# THS7002CPWP_Schematic_2.net
KiCad netlist of a schematic drawn in Altium Designer
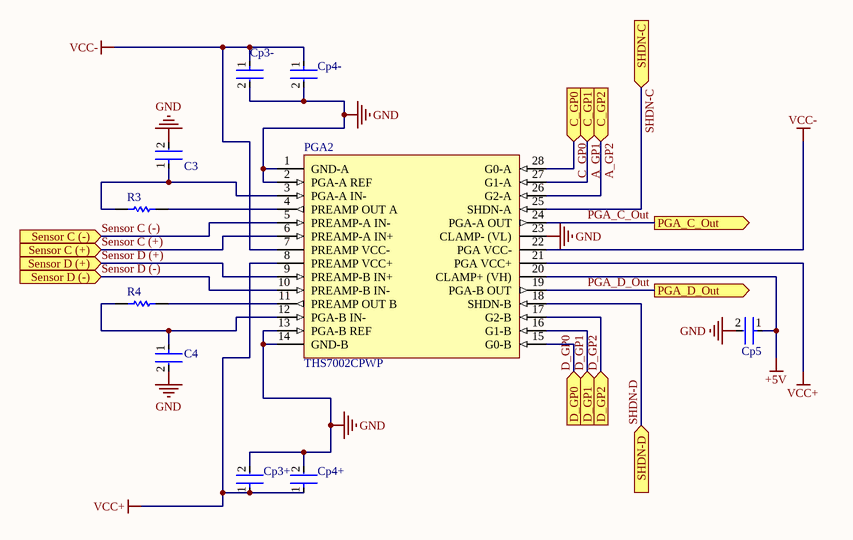
[diagram p0: THS7002CPWP_Schematic_2.SchDoc]

(export (version "E")
  (design (tool "Eeschema 10.0.6"))
  (components
    (comp (ref "C3")
      (value "GRM3195C1H163JA01D")
      (footprint "FP-GRM319-0_15-IPC_A")
      (description "Chip Multilayer Ceramic Capacitors for General Purpose, 1206, 16000pF, C0G, 30ppm/°C, 5%, 50V")
      (fields (field (name "TOLERANCE") "5%"))
      (libsource (lib "Altium Content Vault") (part "b4654b650e69147ec39a6b967a45e02"))
    )
    (comp (ref "C4")
      (value "GRM3195C1H163JA01D")
      (footprint "FP-GRM319-0_15-IPC_A")
      (description "Chip Multilayer Ceramic Capacitors for General Purpose, 1206, 16000pF, C0G, 30ppm/°C, 5%, 50V")
      (fields (field (name "TOLERANCE") "5%"))
      (libsource (lib "Altium Content Vault") (part "b4654b650e69147ec39a6b967a45e02"))
    )
    (comp (ref "Cp3+")
      (value "CC0603KRX7R7BB104")
      (footprint "FP-CC0603-DA-MFG")
      (description "CAP CER 0.1UF 16V X7R 0603")
      (fields
        (field (name "OCTOPART") "https://octopart.com/cc0603krx7r7bb104-yageo-192941")
        (field (name "TOLERANCE") "0.1")
      )
      (libsource (lib "Altium Content Vault") (part "11868f565c42a9108669ba33697ecf6"))
    )
    (comp (ref "Cp3-")
      (value "CC0603KRX7R7BB104")
      (footprint "FP-CC0603-DA-MFG")
      (description "CAP CER 0.1UF 16V X7R 0603")
      (fields
        (field (name "OCTOPART") "https://octopart.com/cc0603krx7r7bb104-yageo-192941")
        (field (name "TOLERANCE") "0.1")
      )
      (libsource (lib "Altium Content Vault") (part "11868f565c42a9108669ba33697ecf6"))
    )
    (comp (ref "Cp4+")
      (value "C2012JB1A685K060AC")
      (footprint "FP-C2012-060-0_2-IPC_A")
      (description "Multilayer Ceramic Capacitors 6.8μF ±10% 10V JB SMD 0805")
      (fields (field (name "TOLERANCE") "10%"))
      (libsource (lib "Altium Content Vault") (part "b4654b650e69147ec39a6b967a45e02"))
    )
    (comp (ref "Cp4-")
      (value "C2012JB1A685K060AC")
      (footprint "FP-C2012-060-0_2-IPC_A")
      (description "Multilayer Ceramic Capacitors 6.8μF ±10% 10V JB SMD 0805")
      (fields (field (name "TOLERANCE") "10%"))
      (libsource (lib "Altium Content Vault") (part "b4654b650e69147ec39a6b967a45e02"))
    )
    (comp (ref "Cp5")
      (value "C2012JB1A685K060AC")
      (footprint "FP-C2012-060-0_2-IPC_A")
      (description "Multilayer Ceramic Capacitors 6.8μF ±10% 10V JB SMD 0805")
      (fields (field (name "TOLERANCE") "10%"))
      (libsource (lib "Altium Content Vault") (part "b4654b650e69147ec39a6b967a45e02"))
    )
    (comp (ref "PGA2")
      (value "THS7002CPWP")
      (footprint "PWP0028E_M")
      (fields (field (name "MANUFACTURER") "Texas Instruments"))
      (libsource (lib "THS7002CPWP_Symbol") (part "CMP-0988-00132-2"))
    )
    (comp (ref "R3")
      (value "CRCW08050000Z0EA")
      (footprint "RESC2013X50X30LL20T20")
      (fields (field (name "MANUFACTURER") "Vishay Dale"))
      (libsource (lib "Altium Content Vault") (part "RES"))
    )
    (comp (ref "R4")
      (value "CRCW08050000Z0EA")
      (footprint "RESC2013X50X30LL20T20")
      (fields (field (name "MANUFACTURER") "Vishay Dale"))
      (libsource (lib "Altium Content Vault") (part "RES"))
    )
  )
  (nets
    (net (code "1") (name "+5V") (class "Default")
      (node (ref "Cp5") (pin "1") (pinfunction "1_1") (pintype "passive"))
      (node (ref "PGA2") (pin "20") (pinfunction "CLAMP+_(VH)_20") (pintype "power_in"))
    )
    (net (code "2") (name "/A_GP1") (class "Default")
      (node (ref "PGA2") (pin "27") (pinfunction "G1-A_27") (pintype "input"))
    )
    (net (code "3") (name "/A_GP2") (class "Default")
      (node (ref "PGA2") (pin "26") (pinfunction "G2-A_26") (pintype "input"))
    )
    (net (code "4") (name "/C_GP0") (class "Default")
      (node (ref "PGA2") (pin "28") (pinfunction "G0-A_28") (pintype "input"))
    )
    (net (code "5") (name "/D_GP0") (class "Default")
      (node (ref "PGA2") (pin "15") (pinfunction "G0-B_15") (pintype "input"))
    )
    (net (code "6") (name "/D_GP1") (class "Default")
      (node (ref "PGA2") (pin "16") (pinfunction "G1-B_16") (pintype "input"))
    )
    (net (code "7") (name "/D_GP2") (class "Default")
      (node (ref "PGA2") (pin "17") (pinfunction "G2-B_17") (pintype "input"))
    )
    (net (code "8") (name "/PGA_C_Out") (class "Default")
      (node (ref "PGA2") (pin "24") (pinfunction "PGA-A_OUT_24") (pintype "output"))
    )
    (net (code "9") (name "/PGA_D_Out") (class "Default")
      (node (ref "PGA2") (pin "19") (pinfunction "PGA-B_OUT_19") (pintype "output"))
    )
    (net (code "10") (name "/SHDN-C") (class "Default")
      (node (ref "PGA2") (pin "25") (pinfunction "SHDN-A_25") (pintype "input"))
    )
    (net (code "11") (name "/SHDN-D") (class "Default")
      (node (ref "PGA2") (pin "18") (pinfunction "SHDN-B_18") (pintype "input"))
    )
    (net (code "12") (name "/Sensor C (+)") (class "Default")
      (node (ref "PGA2") (pin "6") (pinfunction "PREAMP-A_IN+_6") (pintype "input"))
    )
    (net (code "13") (name "/Sensor C (-)") (class "Default")
      (node (ref "PGA2") (pin "5") (pinfunction "PREAMP-A_IN-_5") (pintype "input"))
    )
    (net (code "14") (name "/Sensor D (+)") (class "Default")
      (node (ref "PGA2") (pin "9") (pinfunction "PREAMP-B_IN+_9") (pintype "input"))
    )
    (net (code "15") (name "/Sensor D (-)") (class "Default")
      (node (ref "PGA2") (pin "10") (pinfunction "PREAMP-B_IN-_10") (pintype "input"))
    )
    (net (code "16") (name "GND") (class "Default")
      (node (ref "C3") (pin "2") (pinfunction "2_2") (pintype "passive"))
      (node (ref "C4") (pin "2") (pinfunction "2_2") (pintype "passive"))
      (node (ref "Cp3+") (pin "2") (pinfunction "2_2") (pintype "passive"))
      (node (ref "Cp3-") (pin "2") (pinfunction "2_2") (pintype "passive"))
      (node (ref "Cp4+") (pin "2") (pinfunction "2_2") (pintype "passive"))
      (node (ref "Cp4-") (pin "2") (pinfunction "2_2") (pintype "passive"))
      (node (ref "Cp5") (pin "2") (pinfunction "2_2") (pintype "passive"))
      (node (ref "PGA2") (pin "1") (pinfunction "GND-A_1") (pintype "power_in"))
      (node (ref "PGA2") (pin "13") (pinfunction "PGA-B_REF_13") (pintype "input"))
      (node (ref "PGA2") (pin "14") (pinfunction "GND-B_14") (pintype "power_in"))
      (node (ref "PGA2") (pin "2") (pinfunction "PGA-A_REF_2") (pintype "input"))
      (node (ref "PGA2") (pin "23") (pinfunction "CLAMP-_(VL)_23") (pintype "power_in"))
    )
    (net (code "17") (name "Net-(PGA2-PGA-A_IN-)") (class "Default")
      (node (ref "C3") (pin "1") (pinfunction "1_1") (pintype "passive"))
      (node (ref "PGA2") (pin "3") (pinfunction "PGA-A_IN-_3") (pintype "input"))
      (node (ref "R3") (pin "1") (pinfunction "1_1") (pintype "passive"))
    )
    (net (code "18") (name "Net-(PGA2-PGA-B_IN-)") (class "Default")
      (node (ref "C4") (pin "1") (pinfunction "1_1") (pintype "passive"))
      (node (ref "PGA2") (pin "12") (pinfunction "PGA-B_IN-_12") (pintype "input"))
      (node (ref "R4") (pin "1") (pinfunction "1_1") (pintype "passive"))
    )
    (net (code "19") (name "Net-(PGA2-PREAMP_OUT_A)") (class "Default")
      (node (ref "PGA2") (pin "4") (pinfunction "PREAMP_OUT_A_4") (pintype "output"))
      (node (ref "R3") (pin "2") (pinfunction "2_2") (pintype "passive"))
    )
    (net (code "20") (name "Net-(PGA2-PREAMP_OUT_B)") (class "Default")
      (node (ref "PGA2") (pin "11") (pinfunction "PREAMP_OUT_B_11") (pintype "output"))
      (node (ref "R4") (pin "2") (pinfunction "2_2") (pintype "passive"))
    )
    (net (code "21") (name "VCC+") (class "Default")
      (node (ref "Cp3+") (pin "1") (pinfunction "1_1") (pintype "passive"))
      (node (ref "Cp4+") (pin "1") (pinfunction "1_1") (pintype "passive"))
      (node (ref "PGA2") (pin "21") (pinfunction "PGA_VCC+_21") (pintype "power_in"))
      (node (ref "PGA2") (pin "8") (pinfunction "PREAMP_VCC+_8") (pintype "power_in"))
    )
    (net (code "22") (name "VCC-") (class "Default")
      (node (ref "Cp3-") (pin "1") (pinfunction "1_1") (pintype "passive"))
      (node (ref "Cp4-") (pin "1") (pinfunction "1_1") (pintype "passive"))
      (node (ref "PGA2") (pin "22") (pinfunction "PGA_VCC-_22") (pintype "power_in"))
      (node (ref "PGA2") (pin "7") (pinfunction "PREAMP_VCC-_7") (pintype "power_in"))
    )
  )
)
